# HV.net
KiCad netlist of a schematic drawn in Altium Designer
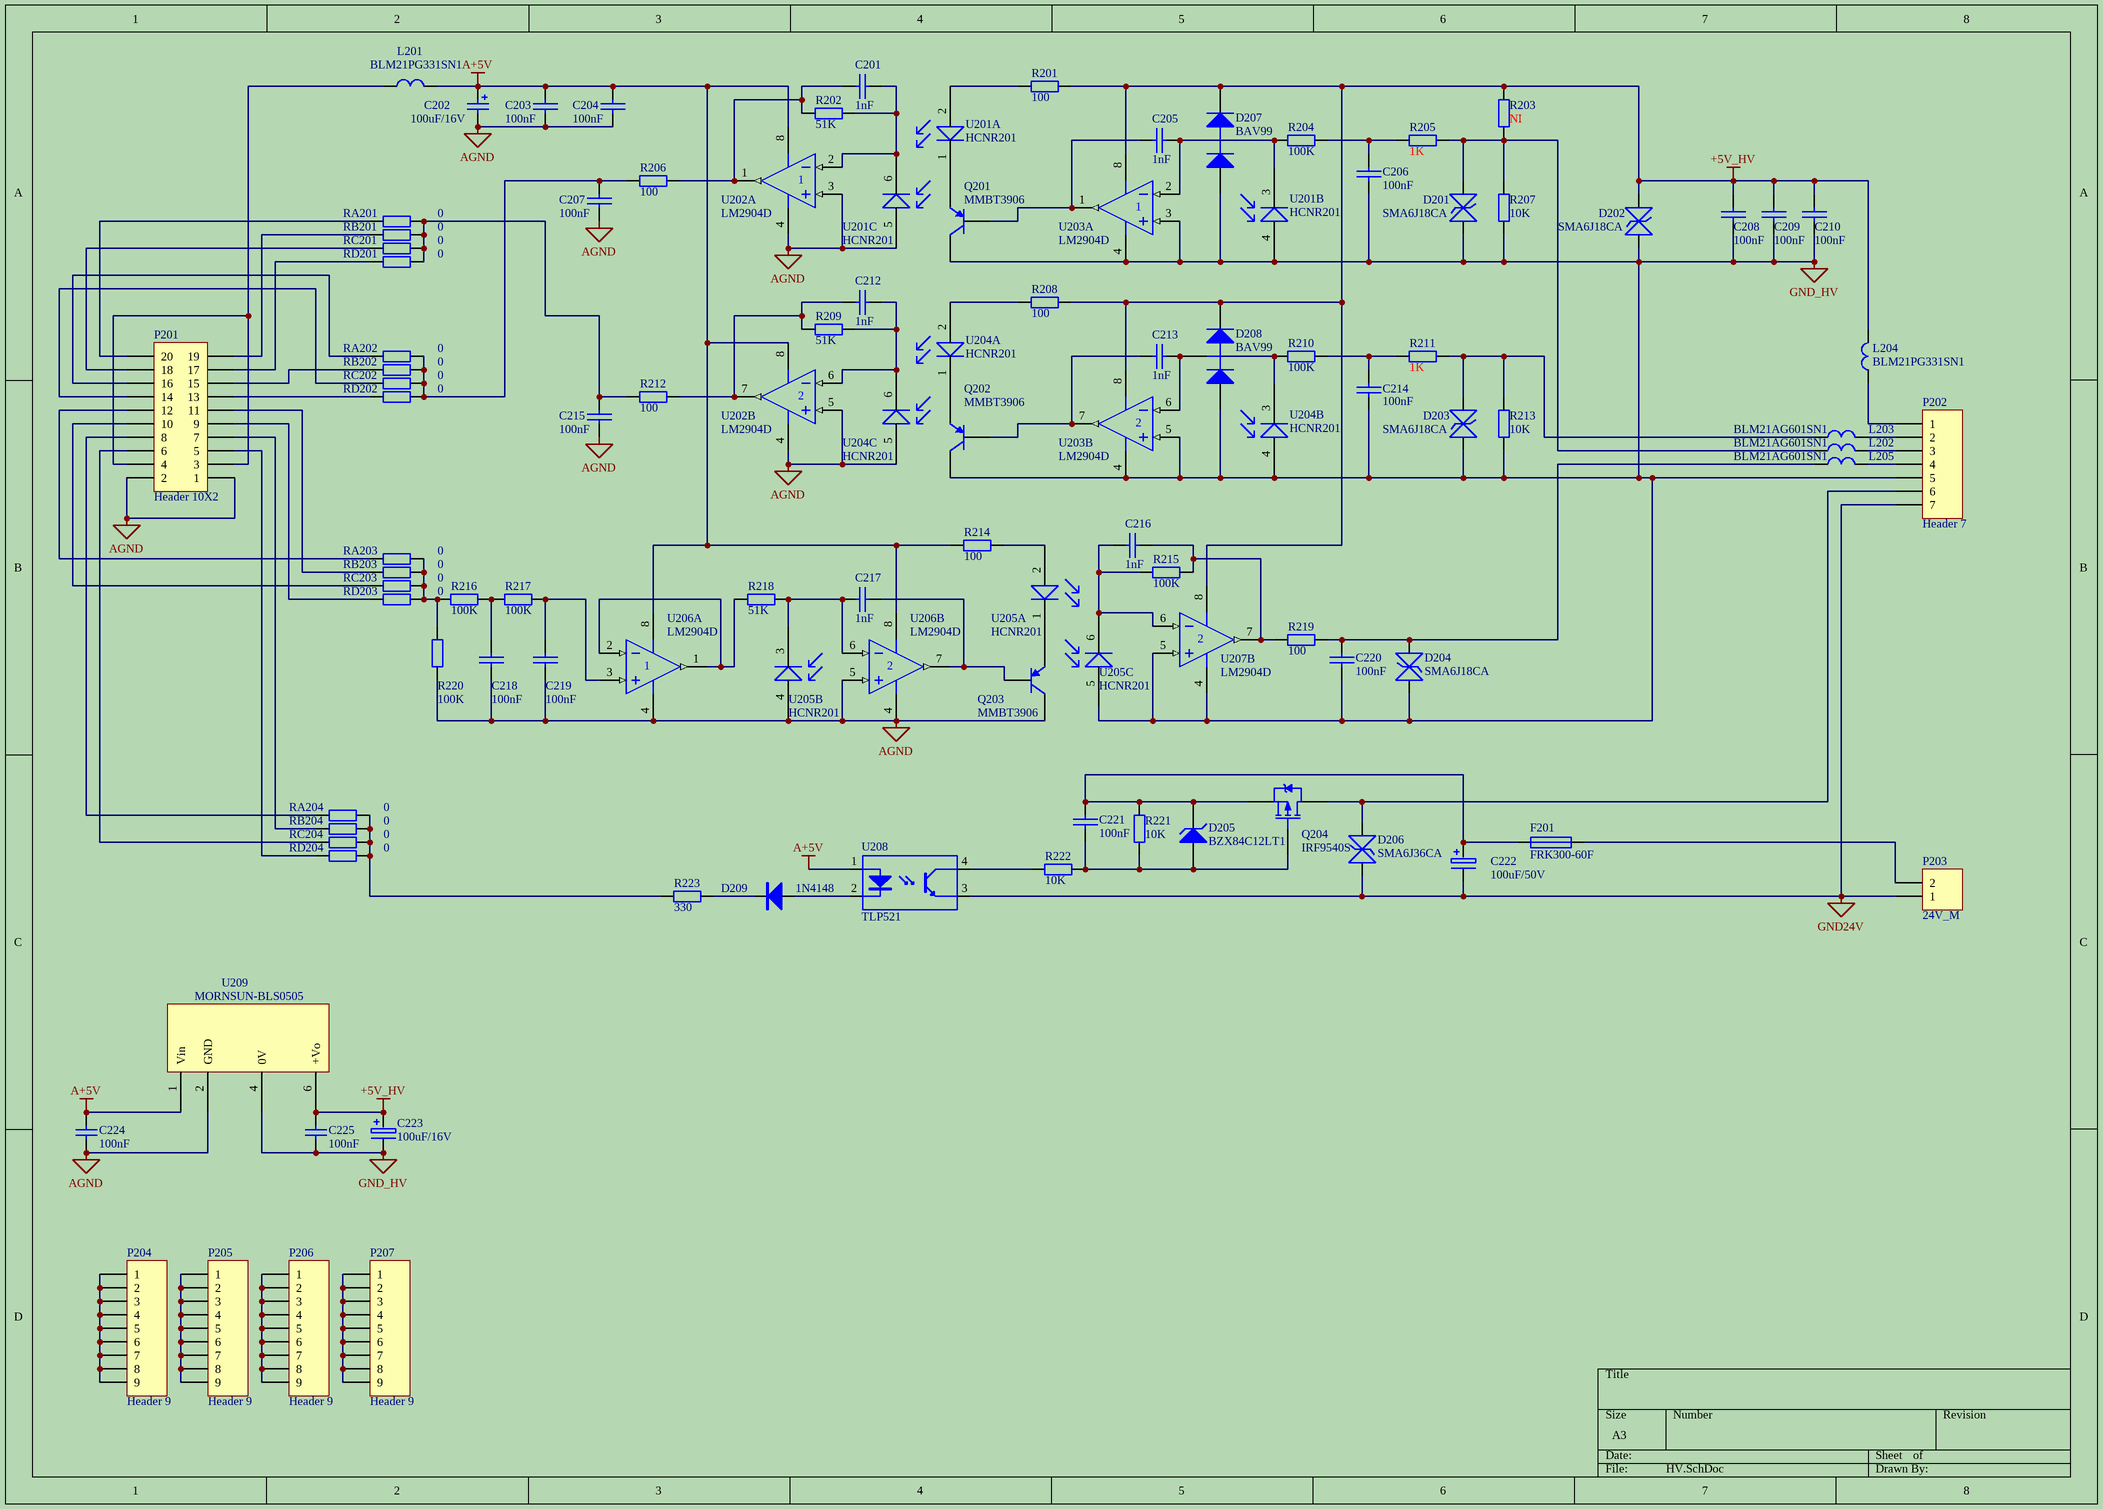
[diagram p0: HV.SchDoc]

(export (version "E")
  (design (tool "Eeschema 10.0.6"))
  (components
    (comp (ref "C201")
      (value "1nF")
      (footprint "贴片元器件:C0805")
      (description "Capacitor")
      (libsource (lib "*") (part "CAP"))
    )
    (comp (ref "C202")
      (value "100uF/16V")
      (footprint "CD1/2")
      (description "Polarized Capacitor (Axial)")
      (fields (field (name "PUBLISHER") "Altium Limited"))
      (libsource (lib "Miscellaneous Devices") (part "Cap Pol2"))
    )
    (comp (ref "C203")
      (value "100nF")
      (footprint "贴片元器件:C0805")
      (description "Capacitor")
      (libsource (lib "*") (part "CC"))
    )
    (comp (ref "C204")
      (value "100nF")
      (footprint "贴片元器件:C0805")
      (description "Capacitor")
      (libsource (lib "*") (part "CC"))
    )
    (comp (ref "C205")
      (value "1nF")
      (footprint "C0805")
      (description "Capacitor")
      (libsource (lib "*") (part "CAP"))
    )
    (comp (ref "C206")
      (value "100nF")
      (footprint "贴片元器件:C0805")
      (description "Capacitor")
      (libsource (lib "*") (part "CC"))
    )
    (comp (ref "C207")
      (value "100nF")
      (footprint "贴片元器件:C0805")
      (description "Capacitor")
      (libsource (lib "*") (part "CC"))
    )
    (comp (ref "C208")
      (value "100nF")
      (footprint "贴片元器件:C0805")
      (description "Capacitor")
      (libsource (lib "*") (part "CC"))
    )
    (comp (ref "C209")
      (value "100nF")
      (footprint "贴片元器件:C0805")
      (description "Capacitor")
      (libsource (lib "*") (part "CC"))
    )
    (comp (ref "C210")
      (value "100nF")
      (footprint "贴片元器件:C0805")
      (description "Capacitor")
      (libsource (lib "*") (part "CC"))
    )
    (comp (ref "C212")
      (value "1nF")
      (footprint "贴片元器件:C0805")
      (description "Capacitor")
      (libsource (lib "*") (part "CAP"))
    )
    (comp (ref "C213")
      (value "1nF")
      (footprint "C0805")
      (description "Capacitor")
      (libsource (lib "*") (part "CAP"))
    )
    (comp (ref "C214")
      (value "100nF")
      (footprint "贴片元器件:C0805")
      (description "Capacitor")
      (libsource (lib "*") (part "CC"))
    )
    (comp (ref "C215")
      (value "100nF")
      (footprint "贴片元器件:C0805")
      (description "Capacitor")
      (libsource (lib "*") (part "CC"))
    )
    (comp (ref "C216")
      (value "1nF")
      (footprint "贴片元器件:C0805")
      (description "Capacitor")
      (libsource (lib "*") (part "CAP"))
    )
    (comp (ref "C217")
      (value "1nF")
      (footprint "C0805")
      (description "Capacitor")
      (libsource (lib "*") (part "CAP"))
    )
    (comp (ref "C218")
      (value "100nF")
      (footprint "贴片元器件:C0805")
      (description "Capacitor")
      (libsource (lib "*") (part "CC"))
    )
    (comp (ref "C219")
      (value "100nF")
      (footprint "贴片元器件:C0805")
      (description "Capacitor")
      (libsource (lib "*") (part "CC"))
    )
    (comp (ref "C220")
      (value "100nF")
      (footprint "贴片元器件:C0805")
      (description "Capacitor")
      (libsource (lib "*") (part "CC"))
    )
    (comp (ref "C221")
      (value "100nF")
      (footprint "贴片元器件:C0805")
      (description "Capacitor")
      (libsource (lib "*") (part "CC"))
    )
    (comp (ref "C222")
      (value "100uF/50V")
      (footprint "CD2/4")
      (description "Electrolytic Capacitor")
      (libsource (lib "Devices") (part "CD1"))
    )
    (comp (ref "C223")
      (value "100uF/16V")
      (footprint "CD1/2")
      (description "Electrolytic Capacitor")
      (libsource (lib "Devices") (part "CD1"))
    )
    (comp (ref "C224")
      (value "100nF")
      (footprint "贴片元器件:C0805")
      (description "Capacitor")
      (fields (field (name "PUBLISHER") "Altium Limited"))
      (libsource (lib "Miscellaneous Devices") (part "Cap"))
    )
    (comp (ref "C225")
      (value "100nF")
      (footprint "贴片元器件:C0805")
      (description "Capacitor")
      (fields (field (name "PUBLISHER") "Altium Limited"))
      (libsource (lib "Miscellaneous Devices") (part "Cap"))
    )
    (comp (ref "D201") (value "SMA6J18CA") (footprint "SMA") (libsource (lib "IC") (part "TVS")))
    (comp (ref "D202") (value "SMA6J18CA") (footprint "SMA") (libsource (lib "IC") (part "TVS")))
    (comp (ref "D203") (value "SMA6J18CA") (footprint "SMA") (libsource (lib "IC") (part "TVS")))
    (comp (ref "D204") (value "SMA6J18CA") (footprint "SMA") (libsource (lib "IC") (part "TVS")))
    (comp (ref "D205")
      (value "BZX84C12LT1")
      (footprint "318-07")
      (description "Zener Voltage Regulator Diode")
      (fields (field (name "PUBLISHER") "Altium Limited"))
      (libsource (lib "Motorola Discrete Diode") (part "BZX84C12LT1"))
    )
    (comp (ref "D206") (value "SMA6J36CA") (footprint "SMA") (libsource (lib "IC") (part "TVS")))
    (comp (ref "D207")
      (value "BAV99")
      (footprint "SOT-23")
      (description "Silicon Switching Diode Array for High-Speed Switching")
      (fields (field (name "PUBLISHER") "Altium Limited"))
      (libsource (lib "Infineon Discrete Diode") (part "BAV99"))
    )
    (comp (ref "D208")
      (value "BAV99")
      (footprint "SOT-23")
      (description "Silicon Switching Diode Array for High-Speed Switching")
      (fields (field (name "PUBLISHER") "Altium Limited"))
      (libsource (lib "Infineon Discrete Diode") (part "BAV99"))
    )
    (comp (ref "D209") (value "1N4148") (footprint "D1206") (libsource (lib "Devices") (part "2JG")))
    (comp (ref "F201")
      (value "FRK300-60F")
      (footprint "RAD-0.2")
      (description "Fuse")
      (libsource (lib "Devices") (part "FUSE1"))
    )
    (comp (ref "L201") (value "BLM21PG331SN1") (footprint "L0805") (libsource (lib "Devices") (part "L1")))
    (comp (ref "L202") (value "BLM21AG601SN1") (footprint "L0805") (libsource (lib "Devices") (part "L1")))
    (comp (ref "L203") (value "BLM21AG601SN1") (footprint "L0805") (libsource (lib "Devices") (part "L1")))
    (comp (ref "L204") (value "BLM21PG331SN1") (footprint "L0805") (libsource (lib "Devices") (part "L1")))
    (comp (ref "L205") (value "BLM21AG601SN1") (footprint "L0805") (libsource (lib "") (part "L1_1")))
    (comp (ref "P201")
      (value "Header 10X2")
      (footprint "IDC20-EJ")
      (description "Header, 10-Pin, Dual row")
      (fields (field (name "PUBLISHER") "Altium Limited"))
      (libsource (lib "Miscellaneous Connectors") (part "Header 10X2"))
    )
    (comp (ref "P202")
      (value "Header 7")
      (footprint "3.96-7")
      (description "Header, 7-Pin")
      (fields (field (name "PUBLISHER") "Altium Limited"))
      (libsource (lib "Miscellaneous Connectors") (part "Header 7"))
    )
    (comp (ref "P203")
      (value "24V_M")
      (footprint "3.96-2")
      (description "Header, 2-Pin")
      (fields (field (name "PUBLISHER") "Altium Limited"))
      (libsource (lib "Miscellaneous Connectors") (part "Header 2"))
    )
    (comp (ref "P204")
      (value "Header 9")
      (footprint "LK")
      (description "Header, 9-Pin")
      (fields (field (name "PUBLISHER") "Altium Limited"))
      (libsource (lib "Miscellaneous Connectors") (part "Header 9"))
    )
    (comp (ref "P205")
      (value "Header 9")
      (footprint "LK")
      (description "Header, 9-Pin")
      (fields (field (name "PUBLISHER") "Altium Limited"))
      (libsource (lib "Miscellaneous Connectors") (part "Header 9"))
    )
    (comp (ref "P206")
      (value "Header 9")
      (footprint "LK")
      (description "Header, 9-Pin")
      (fields (field (name "PUBLISHER") "Altium Limited"))
      (libsource (lib "Miscellaneous Connectors") (part "Header 9"))
    )
    (comp (ref "P207")
      (value "Header 9")
      (footprint "LK")
      (description "Header, 9-Pin")
      (fields (field (name "PUBLISHER") "Altium Limited"))
      (libsource (lib "Miscellaneous Connectors") (part "Header 9"))
    )
    (comp (ref "Q201")
      (value "MMBT3906")
      (footprint "SOT23_N")
      (description "PNP Switching Transistor")
      (fields (field (name "PUBLISHER") "Altium Limited"))
      (libsource (lib "Philips Discrete BJT - Low Power") (part "MMBT3906"))
    )
    (comp (ref "Q202")
      (value "MMBT3906")
      (footprint "SOT23_N")
      (description "PNP Switching Transistor")
      (fields (field (name "PUBLISHER") "Altium Limited"))
      (libsource (lib "Philips Discrete BJT - Low Power") (part "MMBT3906"))
    )
    (comp (ref "Q203")
      (value "MMBT3906")
      (footprint "SOT23_N")
      (description "PNP Switching Transistor")
      (fields (field (name "PUBLISHER") "Altium Limited"))
      (libsource (lib "Philips Discrete BJT - Low Power") (part "MMBT3906"))
    )
    (comp (ref "Q204")
      (value "IRF9540S")
      (footprint "D2PAK_N")
      (description "HEXFET P-Channel Power MOSFET")
      (fields (field (name "PUBLISHER") "Altium Limited"))
      (libsource (lib "IR Discrete MOSFET - Power") (part "IRF9540S"))
    )
    (comp (ref "R201")
      (value "100")
      (footprint "R0805")
      (description "Resistor")
      (fields (field (name "PUBLISHER") "Altium Limited"))
      (libsource (lib "") (part "Res2_1"))
    )
    (comp (ref "R202")
      (value "51K")
      (footprint "R0805")
      (description "Resistor")
      (fields (field (name "PUBLISHER") "Altium Limited"))
      (libsource (lib "") (part "Res2_2"))
    )
    (comp (ref "R203")
      (value "NI")
      (footprint "R0805")
      (description "Resistor")
      (fields (field (name "PUBLISHER") "Altium Limited"))
      (libsource (lib "") (part "Res2_3"))
    )
    (comp (ref "R204")
      (value "100K")
      (footprint "R0805")
      (description "Resistor")
      (fields (field (name "PUBLISHER") "Altium Limited"))
      (libsource (lib "") (part "Res2_2"))
    )
    (comp (ref "R205")
      (value "1K")
      (footprint "R0805")
      (description "Resistor")
      (fields (field (name "PUBLISHER") "Altium Limited"))
      (libsource (lib "") (part "Res2_2"))
    )
    (comp (ref "R206")
      (value "100")
      (footprint "R0805")
      (description "Resistor")
      (fields (field (name "PUBLISHER") "Altium Limited"))
      (libsource (lib "") (part "Res2_1"))
    )
    (comp (ref "R207")
      (value "10K")
      (footprint "R0805")
      (description "Resistor")
      (fields (field (name "PUBLISHER") "Altium Limited"))
      (libsource (lib "") (part "Res2_4"))
    )
    (comp (ref "R208")
      (value "100")
      (footprint "R0805")
      (description "Resistor")
      (fields (field (name "PUBLISHER") "Altium Limited"))
      (libsource (lib "") (part "Res2_1"))
    )
    (comp (ref "R209")
      (value "51K")
      (footprint "R0805")
      (description "Resistor")
      (fields (field (name "PUBLISHER") "Altium Limited"))
      (libsource (lib "") (part "Res2_2"))
    )
    (comp (ref "R210")
      (value "100K")
      (footprint "R0805")
      (description "Resistor")
      (fields (field (name "PUBLISHER") "Altium Limited"))
      (libsource (lib "") (part "Res2_2"))
    )
    (comp (ref "R211")
      (value "1K")
      (footprint "R0805")
      (description "Resistor")
      (fields (field (name "PUBLISHER") "Altium Limited"))
      (libsource (lib "") (part "Res2_2"))
    )
    (comp (ref "R212")
      (value "100")
      (footprint "R0805")
      (description "Resistor")
      (fields (field (name "PUBLISHER") "Altium Limited"))
      (libsource (lib "") (part "Res2_1"))
    )
    (comp (ref "R213")
      (value "10K")
      (footprint "R0805")
      (description "Resistor")
      (fields (field (name "PUBLISHER") "Altium Limited"))
      (libsource (lib "") (part "Res2_4"))
    )
    (comp (ref "R214")
      (value "100")
      (footprint "R0805")
      (description "Resistor")
      (fields (field (name "PUBLISHER") "Altium Limited"))
      (libsource (lib "") (part "Res2_5"))
    )
    (comp (ref "R215")
      (value "100K")
      (footprint "R0805")
      (description "Resistor")
      (fields (field (name "PUBLISHER") "Altium Limited"))
      (libsource (lib "") (part "Res2_3"))
    )
    (comp (ref "R216")
      (value "100K")
      (footprint "R0805")
      (description "Resistor")
      (fields (field (name "PUBLISHER") "Altium Limited"))
      (libsource (lib "") (part "Res2_3"))
    )
    (comp (ref "R217")
      (value "100K")
      (footprint "R0805")
      (description "Resistor")
      (fields (field (name "PUBLISHER") "Altium Limited"))
      (libsource (lib "") (part "Res2_3"))
    )
    (comp (ref "R218")
      (value "51K")
      (footprint "R0805")
      (description "Resistor")
      (fields (field (name "PUBLISHER") "Altium Limited"))
      (libsource (lib "") (part "Res2_3"))
    )
    (comp (ref "R219")
      (value "100")
      (footprint "R0805")
      (description "Resistor")
      (fields (field (name "PUBLISHER") "Altium Limited"))
      (libsource (lib "") (part "Res2_5"))
    )
    (comp (ref "R220")
      (value "100K")
      (footprint "R0805")
      (description "Resistor")
      (fields (field (name "PUBLISHER") "Altium Limited"))
      (libsource (lib "") (part "Res2_4"))
    )
    (comp (ref "R221")
      (value "10K")
      (footprint "R0805")
      (description "Resistor")
      (fields (field (name "PUBLISHER") "Altium Limited"))
      (libsource (lib "Miscellaneous Devices") (part "Res2"))
    )
    (comp (ref "R222")
      (value "10K")
      (footprint "R0805")
      (description "Resistor")
      (fields (field (name "PUBLISHER") "Altium Limited"))
      (libsource (lib "") (part "Res2_6"))
    )
    (comp (ref "R223")
      (value "330")
      (footprint "R0805")
      (description "Resistor")
      (fields (field (name "PUBLISHER") "Altium Limited"))
      (libsource (lib "") (part "Res2_5"))
    )
    (comp (ref "RA201")
      (value "0")
      (footprint "R0805")
      (description "Resistor")
      (fields (field (name "PUBLISHER") "Altium Limited"))
      (libsource (lib "") (part "Res2_1"))
    )
    (comp (ref "RA202")
      (value "0")
      (footprint "R0805")
      (description "Resistor")
      (fields (field (name "PUBLISHER") "Altium Limited"))
      (libsource (lib "") (part "Res2_1"))
    )
    (comp (ref "RA203")
      (value "0")
      (footprint "R0805")
      (description "Resistor")
      (fields (field (name "PUBLISHER") "Altium Limited"))
      (libsource (lib "") (part "Res2_1"))
    )
    (comp (ref "RA204")
      (value "0")
      (footprint "R0805")
      (description "Resistor")
      (fields (field (name "PUBLISHER") "Altium Limited"))
      (libsource (lib "") (part "Res2_1"))
    )
    (comp (ref "RB201")
      (value "0")
      (footprint "R0805")
      (description "Resistor")
      (fields (field (name "PUBLISHER") "Altium Limited"))
      (libsource (lib "") (part "Res2_1"))
    )
    (comp (ref "RB202")
      (value "0")
      (footprint "R0805")
      (description "Resistor")
      (fields (field (name "PUBLISHER") "Altium Limited"))
      (libsource (lib "") (part "Res2_1"))
    )
    (comp (ref "RB203")
      (value "0")
      (footprint "R0805")
      (description "Resistor")
      (fields (field (name "PUBLISHER") "Altium Limited"))
      (libsource (lib "") (part "Res2_1"))
    )
    (comp (ref "RB204")
      (value "0")
      (footprint "R0805")
      (description "Resistor")
      (fields (field (name "PUBLISHER") "Altium Limited"))
      (libsource (lib "") (part "Res2_1"))
    )
    (comp (ref "RC201")
      (value "0")
      (footprint "R0805")
      (description "Resistor")
      (fields (field (name "PUBLISHER") "Altium Limited"))
      (libsource (lib "") (part "Res2_1"))
    )
    (comp (ref "RC202")
      (value "0")
      (footprint "R0805")
      (description "Resistor")
      (fields (field (name "PUBLISHER") "Altium Limited"))
      (libsource (lib "") (part "Res2_1"))
    )
    (comp (ref "RC203")
      (value "0")
      (footprint "R0805")
      (description "Resistor")
      (fields (field (name "PUBLISHER") "Altium Limited"))
      (libsource (lib "") (part "Res2_1"))
    )
    (comp (ref "RC204")
      (value "0")
      (footprint "R0805")
      (description "Resistor")
      (fields (field (name "PUBLISHER") "Altium Limited"))
      (libsource (lib "") (part "Res2_1"))
    )
    (comp (ref "RD201")
      (value "0")
      (footprint "R0805")
      (description "Resistor")
      (fields (field (name "PUBLISHER") "Altium Limited"))
      (libsource (lib "") (part "Res2_1"))
    )
    (comp (ref "RD202")
      (value "0")
      (footprint "R0805")
      (description "Resistor")
      (fields (field (name "PUBLISHER") "Altium Limited"))
      (libsource (lib "") (part "Res2_1"))
    )
    (comp (ref "RD203")
      (value "0")
      (footprint "R0805")
      (description "Resistor")
      (fields (field (name "PUBLISHER") "Altium Limited"))
      (libsource (lib "") (part "Res2_1"))
    )
    (comp (ref "RD204")
      (value "0")
      (footprint "R0805")
      (description "Resistor")
      (fields (field (name "PUBLISHER") "Altium Limited"))
      (libsource (lib "") (part "Res2_1"))
    )
    (comp (ref "U201") (value "HCNR201") (footprint "DIP-8-1") (libsource (lib "*") (part "HCNR201")))
    (comp (ref "U202")
      (value "LM2904D")
      (footprint "751-02_N")
      (description "Dual Low-Power Operational Amplifier")
      (fields (field (name "PUBLISHER") "Altium Limited"))
      (libsource (lib "Motorola Amplifier Operational Amplifier") (part "LM2904D"))
    )
    (comp (ref "U203")
      (value "LM2904D")
      (footprint "751-02_N")
      (description "Dual Low-Power Operational Amplifier")
      (fields (field (name "PUBLISHER") "Altium Limited"))
      (libsource (lib "Motorola Amplifier Operational Amplifier") (part "LM2904D"))
    )
    (comp (ref "U204") (value "HCNR201") (footprint "DIP-8-1") (libsource (lib "*") (part "HCNR201")))
    (comp (ref "U205") (value "HCNR201") (footprint "DIP-8-1") (libsource (lib "*") (part "HCNR201")))
    (comp (ref "U206")
      (value "LM2904D")
      (footprint "751-02_N")
      (description "Dual Low-Power Operational Amplifier")
      (fields (field (name "PUBLISHER") "Altium Limited"))
      (libsource (lib "Motorola Amplifier Operational Amplifier") (part "LM2904D"))
    )
    (comp (ref "U207")
      (value "LM2904D")
      (footprint "751-02_N")
      (description "Dual Low-Power Operational Amplifier")
      (fields (field (name "PUBLISHER") "Altium Limited"))
      (libsource (lib "Motorola Amplifier Operational Amplifier") (part "LM2904D"))
    )
    (comp (ref "U208") (value "TLP521") (footprint "DIP4") (libsource (lib "IC") (part "TLP521")))
    (comp (ref "U209")
      (value "MORNSUN-BLS0505")
      (footprint "MORNSUN-BLS")
      (description "MORNSUN Fixed input,Isolated,Unregulated Series DC/DC")
      (libsource (lib "稳压器件") (part "MORNSUN-BLS"))
    )
  )
  (nets
    (net (code "1") (name "+5V_HV") (class "Default")
      (node (ref "C208") (pin "2") (pinfunction "2_2") (pintype "passive"))
      (node (ref "C209") (pin "2") (pinfunction "2_2") (pintype "passive"))
      (node (ref "C210") (pin "2") (pinfunction "2_2") (pintype "passive"))
      (node (ref "C223") (pin "1") (pinfunction "1_1") (pintype "passive"))
      (node (ref "C225") (pin "1") (pinfunction "1_1") (pintype "passive"))
      (node (ref "D202") (pin "1") (pinfunction "1_1") (pintype "passive"))
      (node (ref "D207") (pin "2") (pinfunction "K_2") (pintype "passive"))
      (node (ref "D208") (pin "2") (pinfunction "K_2") (pintype "passive"))
      (node (ref "L204") (pin "2") (pinfunction "2_2") (pintype "passive"))
      (node (ref "R201") (pin "1") (pinfunction "1_1") (pintype "passive"))
      (node (ref "R203") (pin "1") (pinfunction "1_1") (pintype "passive"))
      (node (ref "R208") (pin "1") (pinfunction "1_1") (pintype "passive"))
      (node (ref "U203") (pin "8") (pinfunction "V+_8") (pintype "power_in"))
      (node (ref "U207") (pin "8") (pinfunction "V+_8") (pintype "power_in"))
      (node (ref "U209") (pin "6") (pinfunction "+Vo_6") (pintype "passive"))
    )
    (net (code "2") (name "A+5V") (class "Default")
      (node (ref "C202") (pin "1") (pinfunction "1_1") (pintype "passive"))
      (node (ref "C203") (pin "2") (pinfunction "2_2") (pintype "passive"))
      (node (ref "C204") (pin "2") (pinfunction "2_2") (pintype "passive"))
      (node (ref "C224") (pin "1") (pinfunction "1_1") (pintype "passive"))
      (node (ref "L201") (pin "2") (pinfunction "2_2") (pintype "passive"))
      (node (ref "R214") (pin "1") (pinfunction "1_1") (pintype "passive"))
      (node (ref "U202") (pin "8") (pinfunction "V+_8") (pintype "power_in"))
      (node (ref "U206") (pin "8") (pinfunction "V+_8") (pintype "power_in"))
      (node (ref "U208") (pin "1") (pinfunction "A_1") (pintype "passive"))
      (node (ref "U209") (pin "1") (pinfunction "Vin_1") (pintype "passive"))
    )
    (net (code "3") (name "AGND") (class "Default")
      (node (ref "C202") (pin "2") (pinfunction "2_2") (pintype "passive"))
      (node (ref "C203") (pin "1") (pinfunction "1_1") (pintype "passive"))
      (node (ref "C204") (pin "1") (pinfunction "1_1") (pintype "passive"))
      (node (ref "C207") (pin "1") (pinfunction "1_1") (pintype "passive"))
      (node (ref "C215") (pin "1") (pinfunction "1_1") (pintype "passive"))
      (node (ref "C218") (pin "1") (pinfunction "1_1") (pintype "passive"))
      (node (ref "C219") (pin "1") (pinfunction "1_1") (pintype "passive"))
      (node (ref "C224") (pin "2") (pinfunction "2_2") (pintype "passive"))
      (node (ref "P201") (pin "1") (pinfunction "1_1") (pintype "passive"))
      (node (ref "P201") (pin "2") (pinfunction "2_2") (pintype "passive"))
      (node (ref "Q203") (pin "3") (pinfunction "C_3") (pintype "passive"))
      (node (ref "R220") (pin "1") (pinfunction "1_1") (pintype "passive"))
      (node (ref "U201") (pin "5") (pinfunction "+_5") (pintype "passive"))
      (node (ref "U202") (pin "3") (pinfunction "IN+_3") (pintype "input"))
      (node (ref "U202") (pin "4") (pinfunction "V-_4") (pintype "power_in"))
      (node (ref "U202") (pin "5") (pinfunction "IN+_5") (pintype "input"))
      (node (ref "U204") (pin "5") (pinfunction "+_5") (pintype "passive"))
      (node (ref "U205") (pin "4") (pinfunction "+_4") (pintype "passive"))
      (node (ref "U206") (pin "4") (pinfunction "V-_4") (pintype "power_in"))
      (node (ref "U206") (pin "5") (pinfunction "IN+_5") (pintype "input"))
      (node (ref "U209") (pin "2") (pinfunction "GND_2") (pintype "passive"))
    )
    (net (code "4") (name "GND24V") (class "Default")
      (node (ref "C222") (pin "2") (pinfunction "2_2") (pintype "passive"))
      (node (ref "D206") (pin "2") (pinfunction "2_2") (pintype "passive"))
      (node (ref "P202") (pin "7") (pinfunction "7_7") (pintype "passive"))
      (node (ref "P203") (pin "1") (pinfunction "1_1") (pintype "passive"))
      (node (ref "U208") (pin "3") (pinfunction "E_3") (pintype "passive"))
    )
    (net (code "5") (name "GND_HV") (class "Default")
      (node (ref "C206") (pin "1") (pinfunction "1_1") (pintype "passive"))
      (node (ref "C208") (pin "1") (pinfunction "1_1") (pintype "passive"))
      (node (ref "C209") (pin "1") (pinfunction "1_1") (pintype "passive"))
      (node (ref "C210") (pin "1") (pinfunction "1_1") (pintype "passive"))
      (node (ref "C214") (pin "1") (pinfunction "1_1") (pintype "passive"))
      (node (ref "C220") (pin "1") (pinfunction "1_1") (pintype "passive"))
      (node (ref "C223") (pin "2") (pinfunction "2_2") (pintype "passive"))
      (node (ref "C225") (pin "2") (pinfunction "2_2") (pintype "passive"))
      (node (ref "D201") (pin "2") (pinfunction "2_2") (pintype "passive"))
      (node (ref "D202") (pin "2") (pinfunction "2_2") (pintype "passive"))
      (node (ref "D203") (pin "2") (pinfunction "2_2") (pintype "passive"))
      (node (ref "D204") (pin "2") (pinfunction "2_2") (pintype "passive"))
      (node (ref "D207") (pin "1") (pinfunction "A_1") (pintype "passive"))
      (node (ref "D208") (pin "1") (pinfunction "A_1") (pintype "passive"))
      (node (ref "P202") (pin "5") (pinfunction "5_5") (pintype "passive"))
      (node (ref "Q201") (pin "3") (pinfunction "C_3") (pintype "passive"))
      (node (ref "Q202") (pin "3") (pinfunction "C_3") (pintype "passive"))
      (node (ref "R207") (pin "1") (pinfunction "1_1") (pintype "passive"))
      (node (ref "R213") (pin "1") (pinfunction "1_1") (pintype "passive"))
      (node (ref "U201") (pin "4") (pinfunction "+_4") (pintype "passive"))
      (node (ref "U203") (pin "3") (pinfunction "IN+_3") (pintype "input"))
      (node (ref "U203") (pin "4") (pinfunction "V-_4") (pintype "power_in"))
      (node (ref "U203") (pin "5") (pinfunction "IN+_5") (pintype "input"))
      (node (ref "U204") (pin "4") (pinfunction "+_4") (pintype "passive"))
      (node (ref "U205") (pin "5") (pinfunction "+_5") (pintype "passive"))
      (node (ref "U207") (pin "4") (pinfunction "V-_4") (pintype "power_in"))
      (node (ref "U207") (pin "5") (pinfunction "IN+_5") (pintype "input"))
      (node (ref "U209") (pin "4") (pinfunction "0V_4") (pintype "passive"))
    )
    (net (code "6") (name "Net-(C206-Pad2)") (class "Default")
      (node (ref "C206") (pin "2") (pinfunction "2_2") (pintype "passive"))
      (node (ref "R204") (pin "2") (pinfunction "2_2") (pintype "passive"))
      (node (ref "R205") (pin "1") (pinfunction "1_1") (pintype "passive"))
    )
    (net (code "7") (name "Net-(C207-Pad2)") (class "Default")
      (node (ref "C207") (pin "2") (pinfunction "2_2") (pintype "passive"))
      (node (ref "R206") (pin "2") (pinfunction "2_2") (pintype "passive"))
      (node (ref "RA202") (pin "1") (pinfunction "1_1") (pintype "passive"))
      (node (ref "RB202") (pin "1") (pinfunction "1_1") (pintype "passive"))
      (node (ref "RC202") (pin "1") (pinfunction "1_1") (pintype "passive"))
      (node (ref "RD202") (pin "1") (pinfunction "1_1") (pintype "passive"))
    )
    (net (code "8") (name "Net-(C214-Pad2)") (class "Default")
      (node (ref "C214") (pin "2") (pinfunction "2_2") (pintype "passive"))
      (node (ref "R210") (pin "2") (pinfunction "2_2") (pintype "passive"))
      (node (ref "R211") (pin "1") (pinfunction "1_1") (pintype "passive"))
    )
    (net (code "9") (name "Net-(C215-Pad2)") (class "Default")
      (node (ref "C215") (pin "2") (pinfunction "2_2") (pintype "passive"))
      (node (ref "R212") (pin "2") (pinfunction "2_2") (pintype "passive"))
      (node (ref "RA201") (pin "1") (pinfunction "1_1") (pintype "passive"))
      (node (ref "RB201") (pin "1") (pinfunction "1_1") (pintype "passive"))
      (node (ref "RC201") (pin "1") (pinfunction "1_1") (pintype "passive"))
      (node (ref "RD201") (pin "1") (pinfunction "1_1") (pintype "passive"))
    )
    (net (code "10") (name "Net-(C218-Pad2)") (class "Default")
      (node (ref "C218") (pin "2") (pinfunction "2_2") (pintype "passive"))
      (node (ref "R216") (pin "1") (pinfunction "1_1") (pintype "passive"))
      (node (ref "R217") (pin "2") (pinfunction "2_2") (pintype "passive"))
    )
    (net (code "11") (name "Net-(C220-Pad2)") (class "Default")
      (node (ref "C220") (pin "2") (pinfunction "2_2") (pintype "passive"))
      (node (ref "D204") (pin "1") (pinfunction "1_1") (pintype "passive"))
      (node (ref "L205") (pin "2") (pinfunction "2_2") (pintype "passive"))
      (node (ref "R219") (pin "2") (pinfunction "2_2") (pintype "passive"))
    )
    (net (code "12") (name "Net-(D201-Pad1)") (class "Default")
      (node (ref "D201") (pin "1") (pinfunction "1_1") (pintype "passive"))
      (node (ref "L202") (pin "1") (pinfunction "1_1") (pintype "passive"))
      (node (ref "R203") (pin "2") (pinfunction "2_2") (pintype "passive"))
      (node (ref "R205") (pin "2") (pinfunction "2_2") (pintype "passive"))
      (node (ref "R207") (pin "2") (pinfunction "2_2") (pintype "passive"))
    )
    (net (code "13") (name "Net-(D203-Pad1)") (class "Default")
      (node (ref "D203") (pin "1") (pinfunction "1_1") (pintype "passive"))
      (node (ref "L203") (pin "1") (pinfunction "1_1") (pintype "passive"))
      (node (ref "R211") (pin "2") (pinfunction "2_2") (pintype "passive"))
      (node (ref "R213") (pin "2") (pinfunction "2_2") (pintype "passive"))
    )
    (net (code "14") (name "Net-(D205-A)") (class "Default")
      (node (ref "C221") (pin "1") (pinfunction "1_1") (pintype "passive"))
      (node (ref "D205") (pin "1") (pinfunction "A_1") (pintype "passive"))
      (node (ref "Q204") (pin "1") (pinfunction "G_1") (pintype "passive"))
      (node (ref "R221") (pin "1") (pinfunction "1_1") (pintype "passive"))
      (node (ref "R222") (pin "1") (pinfunction "1_1") (pintype "passive"))
    )
    (net (code "15") (name "Net-(D205-K)") (class "Default")
      (node (ref "C221") (pin "2") (pinfunction "2_2") (pintype "passive"))
      (node (ref "C222") (pin "1") (pinfunction "1_1") (pintype "passive"))
      (node (ref "D205") (pin "3") (pinfunction "K_3") (pintype "passive"))
      (node (ref "F201") (pin "2") (pinfunction "2_2") (pintype "passive"))
      (node (ref "Q204") (pin "3") (pinfunction "S_3") (pintype "passive"))
      (node (ref "R221") (pin "2") (pinfunction "2_2") (pintype "passive"))
    )
    (net (code "16") (name "Net-(D207-C)") (class "Default")
      (node (ref "C205") (pin "1") (pinfunction "1_1") (pintype "passive"))
      (node (ref "D207") (pin "3") (pinfunction "C_3") (pintype "passive"))
      (node (ref "R204") (pin "1") (pinfunction "1_1") (pintype "passive"))
      (node (ref "U201") (pin "3") (pinfunction "-_3") (pintype "passive"))
      (node (ref "U203") (pin "2") (pinfunction "IN-_2") (pintype "input"))
    )
    (net (code "17") (name "Net-(D208-C)") (class "Default")
      (node (ref "C213") (pin "1") (pinfunction "1_1") (pintype "passive"))
      (node (ref "D208") (pin "3") (pinfunction "C_3") (pintype "passive"))
      (node (ref "R210") (pin "1") (pinfunction "1_1") (pintype "passive"))
      (node (ref "U203") (pin "6") (pinfunction "IN-_6") (pintype "input"))
      (node (ref "U204") (pin "3") (pinfunction "-_3") (pintype "passive"))
    )
    (net (code "18") (name "Net-(D209-A)") (class "Default")
      (node (ref "D209") (pin "1") (pinfunction "A_1") (pintype "passive"))
      (node (ref "U208") (pin "2") (pinfunction "K_2") (pintype "passive"))
    )
    (net (code "19") (name "Net-(D209-K)") (class "Default")
      (node (ref "D209") (pin "2") (pinfunction "K_2") (pintype "passive"))
      (node (ref "R223") (pin "2") (pinfunction "2_2") (pintype "passive"))
    )
    (net (code "20") (name "Net-(F201-Pad1)") (class "Default")
      (node (ref "F201") (pin "1") (pinfunction "1_1") (pintype "passive"))
      (node (ref "P203") (pin "2") (pinfunction "2_2") (pintype "passive"))
    )
    (net (code "21") (name "Net-(L201-Pad1)") (class "Default")
      (node (ref "L201") (pin "1") (pinfunction "1_1") (pintype "passive"))
      (node (ref "P201") (pin "3") (pinfunction "3_3") (pintype "passive"))
      (node (ref "P201") (pin "4") (pinfunction "4_4") (pintype "passive"))
    )
    (net (code "22") (name "Net-(L202-Pad2)") (class "Default")
      (node (ref "L202") (pin "2") (pinfunction "2_2") (pintype "passive"))
      (node (ref "P202") (pin "3") (pinfunction "3_3") (pintype "passive"))
    )
    (net (code "23") (name "Net-(L203-Pad2)") (class "Default")
      (node (ref "L203") (pin "2") (pinfunction "2_2") (pintype "passive"))
      (node (ref "P202") (pin "2") (pinfunction "2_2") (pintype "passive"))
    )
    (net (code "24") (name "Net-(L204-Pad1)") (class "Default")
      (node (ref "L204") (pin "1") (pinfunction "1_1") (pintype "passive"))
      (node (ref "P202") (pin "1") (pinfunction "1_1") (pintype "passive"))
    )
    (net (code "25") (name "Net-(L205-Pad1)") (class "Default")
      (node (ref "L205") (pin "1") (pinfunction "1_1") (pintype "passive"))
      (node (ref "P202") (pin "4") (pinfunction "4_4") (pintype "passive"))
    )
    (net (code "26") (name "Net-(P201-Pad5)") (class "Default")
      (node (ref "P201") (pin "5") (pinfunction "5_5") (pintype "passive"))
      (node (ref "RD204") (pin "2") (pinfunction "2_2") (pintype "passive"))
    )
    (net (code "27") (name "Net-(P201-Pad6)") (class "Default")
      (node (ref "P201") (pin "6") (pinfunction "6_6") (pintype "passive"))
      (node (ref "RC204") (pin "2") (pinfunction "2_2") (pintype "passive"))
    )
    (net (code "28") (name "Net-(P201-Pad7)") (class "Default")
      (node (ref "P201") (pin "7") (pinfunction "7_7") (pintype "passive"))
      (node (ref "RB204") (pin "2") (pinfunction "2_2") (pintype "passive"))
    )
    (net (code "29") (name "Net-(P201-Pad8)") (class "Default")
      (node (ref "P201") (pin "8") (pinfunction "8_8") (pintype "passive"))
      (node (ref "RA204") (pin "2") (pinfunction "2_2") (pintype "passive"))
    )
    (net (code "30") (name "Net-(P201-Pad9)") (class "Default")
      (node (ref "P201") (pin "9") (pinfunction "9_9") (pintype "passive"))
      (node (ref "RD203") (pin "2") (pinfunction "2_2") (pintype "passive"))
    )
    (net (code "31") (name "Net-(P201-Pad10)") (class "Default")
      (node (ref "P201") (pin "10") (pinfunction "10_10") (pintype "passive"))
      (node (ref "RC203") (pin "2") (pinfunction "2_2") (pintype "passive"))
    )
    (net (code "32") (name "Net-(P201-Pad11)") (class "Default")
      (node (ref "P201") (pin "11") (pinfunction "11_11") (pintype "passive"))
      (node (ref "RB203") (pin "2") (pinfunction "2_2") (pintype "passive"))
    )
    (net (code "33") (name "Net-(P201-Pad12)") (class "Default")
      (node (ref "P201") (pin "12") (pinfunction "12_12") (pintype "passive"))
      (node (ref "RA203") (pin "2") (pinfunction "2_2") (pintype "passive"))
    )
    (net (code "34") (name "Net-(P201-Pad13)") (class "Default")
      (node (ref "P201") (pin "13") (pinfunction "13_13") (pintype "passive"))
      (node (ref "RD202") (pin "2") (pinfunction "2_2") (pintype "passive"))
    )
    (net (code "35") (name "Net-(P201-Pad14)") (class "Default")
      (node (ref "P201") (pin "14") (pinfunction "14_14") (pintype "passive"))
      (node (ref "RC202") (pin "2") (pinfunction "2_2") (pintype "passive"))
    )
    (net (code "36") (name "Net-(P201-Pad15)") (class "Default")
      (node (ref "P201") (pin "15") (pinfunction "15_15") (pintype "passive"))
      (node (ref "RB202") (pin "2") (pinfunction "2_2") (pintype "passive"))
    )
    (net (code "37") (name "Net-(P201-Pad16)") (class "Default")
      (node (ref "P201") (pin "16") (pinfunction "16_16") (pintype "passive"))
      (node (ref "RA202") (pin "2") (pinfunction "2_2") (pintype "passive"))
    )
    (net (code "38") (name "Net-(P201-Pad17)") (class "Default")
      (node (ref "P201") (pin "17") (pinfunction "17_17") (pintype "passive"))
      (node (ref "RD201") (pin "2") (pinfunction "2_2") (pintype "passive"))
    )
    (net (code "39") (name "Net-(P201-Pad18)") (class "Default")
      (node (ref "P201") (pin "18") (pinfunction "18_18") (pintype "passive"))
      (node (ref "RC201") (pin "2") (pinfunction "2_2") (pintype "passive"))
    )
    (net (code "40") (name "Net-(P201-Pad19)") (class "Default")
      (node (ref "P201") (pin "19") (pinfunction "19_19") (pintype "passive"))
      (node (ref "RB201") (pin "2") (pinfunction "2_2") (pintype "passive"))
    )
    (net (code "41") (name "Net-(P201-Pad20)") (class "Default")
      (node (ref "P201") (pin "20") (pinfunction "20_20") (pintype "passive"))
      (node (ref "RA201") (pin "2") (pinfunction "2_2") (pintype "passive"))
    )
    (net (code "42") (name "Net-(P204-Pad1)") (class "Default")
      (node (ref "P204") (pin "1") (pinfunction "1_1") (pintype "passive"))
      (node (ref "P204") (pin "2") (pinfunction "2_2") (pintype "passive"))
      (node (ref "P204") (pin "3") (pinfunction "3_3") (pintype "passive"))
      (node (ref "P204") (pin "4") (pinfunction "4_4") (pintype "passive"))
      (node (ref "P204") (pin "5") (pinfunction "5_5") (pintype "passive"))
      (node (ref "P204") (pin "6") (pinfunction "6_6") (pintype "passive"))
      (node (ref "P204") (pin "7") (pinfunction "7_7") (pintype "passive"))
      (node (ref "P204") (pin "8") (pinfunction "8_8") (pintype "passive"))
      (node (ref "P204") (pin "9") (pinfunction "9_9") (pintype "passive"))
    )
    (net (code "43") (name "Net-(P205-Pad1)") (class "Default")
      (node (ref "P205") (pin "1") (pinfunction "1_1") (pintype "passive"))
      (node (ref "P205") (pin "2") (pinfunction "2_2") (pintype "passive"))
      (node (ref "P205") (pin "3") (pinfunction "3_3") (pintype "passive"))
      (node (ref "P205") (pin "4") (pinfunction "4_4") (pintype "passive"))
      (node (ref "P205") (pin "5") (pinfunction "5_5") (pintype "passive"))
      (node (ref "P205") (pin "6") (pinfunction "6_6") (pintype "passive"))
      (node (ref "P205") (pin "7") (pinfunction "7_7") (pintype "passive"))
      (node (ref "P205") (pin "8") (pinfunction "8_8") (pintype "passive"))
      (node (ref "P205") (pin "9") (pinfunction "9_9") (pintype "passive"))
    )
    (net (code "44") (name "Net-(P206-Pad1)") (class "Default")
      (node (ref "P206") (pin "1") (pinfunction "1_1") (pintype "passive"))
      (node (ref "P206") (pin "2") (pinfunction "2_2") (pintype "passive"))
      (node (ref "P206") (pin "3") (pinfunction "3_3") (pintype "passive"))
      (node (ref "P206") (pin "4") (pinfunction "4_4") (pintype "passive"))
      (node (ref "P206") (pin "5") (pinfunction "5_5") (pintype "passive"))
      (node (ref "P206") (pin "6") (pinfunction "6_6") (pintype "passive"))
      (node (ref "P206") (pin "7") (pinfunction "7_7") (pintype "passive"))
      (node (ref "P206") (pin "8") (pinfunction "8_8") (pintype "passive"))
      (node (ref "P206") (pin "9") (pinfunction "9_9") (pintype "passive"))
    )
    (net (code "45") (name "Net-(P207-Pad1)") (class "Default")
      (node (ref "P207") (pin "1") (pinfunction "1_1") (pintype "passive"))
      (node (ref "P207") (pin "2") (pinfunction "2_2") (pintype "passive"))
      (node (ref "P207") (pin "3") (pinfunction "3_3") (pintype "passive"))
      (node (ref "P207") (pin "4") (pinfunction "4_4") (pintype "passive"))
      (node (ref "P207") (pin "5") (pinfunction "5_5") (pintype "passive"))
      (node (ref "P207") (pin "6") (pinfunction "6_6") (pintype "passive"))
      (node (ref "P207") (pin "7") (pinfunction "7_7") (pintype "passive"))
      (node (ref "P207") (pin "8") (pinfunction "8_8") (pintype "passive"))
      (node (ref "P207") (pin "9") (pinfunction "9_9") (pintype "passive"))
    )
    (net (code "46") (name "Net-(Q201-B)") (class "Default")
      (node (ref "C205") (pin "2") (pinfunction "2_2") (pintype "passive"))
      (node (ref "Q201") (pin "1") (pinfunction "B_1") (pintype "passive"))
      (node (ref "U203") (pin "1") (pinfunction "OUT_1") (pintype "output"))
    )
    (net (code "47") (name "Net-(Q201-E)") (class "Default")
      (node (ref "Q201") (pin "2") (pinfunction "E_2") (pintype "passive"))
      (node (ref "U201") (pin "1") (pinfunction "-_1") (pintype "passive"))
    )
    (net (code "48") (name "Net-(Q202-B)") (class "Default")
      (node (ref "C213") (pin "2") (pinfunction "2_2") (pintype "passive"))
      (node (ref "Q202") (pin "1") (pinfunction "B_1") (pintype "passive"))
      (node (ref "U203") (pin "7") (pinfunction "OUT_7") (pintype "output"))
    )
    (net (code "49") (name "Net-(Q202-E)") (class "Default")
      (node (ref "Q202") (pin "2") (pinfunction "E_2") (pintype "passive"))
      (node (ref "U204") (pin "1") (pinfunction "-_1") (pintype "passive"))
    )
    (net (code "50") (name "Net-(Q203-B)") (class "Default")
      (node (ref "C217") (pin "2") (pinfunction "2_2") (pintype "passive"))
      (node (ref "Q203") (pin "1") (pinfunction "B_1") (pintype "passive"))
      (node (ref "U206") (pin "7") (pinfunction "OUT_7") (pintype "output"))
    )
    (net (code "51") (name "Net-(Q203-E)") (class "Default")
      (node (ref "Q203") (pin "2") (pinfunction "E_2") (pintype "passive"))
      (node (ref "U205") (pin "1") (pinfunction "-_1") (pintype "passive"))
    )
    (net (code "52") (name "Net-(Q204-D)") (class "Default")
      (node (ref "D206") (pin "1") (pinfunction "1_1") (pintype "passive"))
      (node (ref "P202") (pin "6") (pinfunction "6_6") (pintype "passive"))
      (node (ref "Q204") (pin "2") (pinfunction "D_2") (pintype "passive"))
    )
    (net (code "53") (name "Net-(R216-Pad2)") (class "Default")
      (node (ref "R216") (pin "2") (pinfunction "2_2") (pintype "passive"))
      (node (ref "R220") (pin "2") (pinfunction "2_2") (pintype "passive"))
      (node (ref "RA203") (pin "1") (pinfunction "1_1") (pintype "passive"))
      (node (ref "RB203") (pin "1") (pinfunction "1_1") (pintype "passive"))
      (node (ref "RC203") (pin "1") (pinfunction "1_1") (pintype "passive"))
      (node (ref "RD203") (pin "1") (pinfunction "1_1") (pintype "passive"))
    )
    (net (code "54") (name "Net-(R223-Pad1)") (class "Default")
      (node (ref "R223") (pin "1") (pinfunction "1_1") (pintype "passive"))
      (node (ref "RA204") (pin "1") (pinfunction "1_1") (pintype "passive"))
      (node (ref "RB204") (pin "1") (pinfunction "1_1") (pintype "passive"))
      (node (ref "RC204") (pin "1") (pinfunction "1_1") (pintype "passive"))
      (node (ref "RD204") (pin "1") (pinfunction "1_1") (pintype "passive"))
    )
    (net (code "55") (name "Net-(U201A-+)") (class "Default")
      (node (ref "R201") (pin "2") (pinfunction "2_2") (pintype "passive"))
      (node (ref "U201") (pin "2") (pinfunction "+_2") (pintype "passive"))
    )
    (net (code "56") (name "Net-(U201C--)") (class "Default")
      (node (ref "C201") (pin "1") (pinfunction "1_1") (pintype "passive"))
      (node (ref "R202") (pin "2") (pinfunction "2_2") (pintype "passive"))
      (node (ref "U201") (pin "6") (pinfunction "-_6") (pintype "passive"))
      (node (ref "U202") (pin "2") (pinfunction "IN-_2") (pintype "input"))
    )
    (net (code "57") (name "Net-(U202A-OUT)") (class "Default")
      (node (ref "C201") (pin "2") (pinfunction "2_2") (pintype "passive"))
      (node (ref "R202") (pin "1") (pinfunction "1_1") (pintype "passive"))
      (node (ref "R206") (pin "1") (pinfunction "1_1") (pintype "passive"))
      (node (ref "U202") (pin "1") (pinfunction "OUT_1") (pintype "output"))
    )
    (net (code "58") (name "Net-(U202B-IN-)") (class "Default")
      (node (ref "C212") (pin "1") (pinfunction "1_1") (pintype "passive"))
      (node (ref "R209") (pin "2") (pinfunction "2_2") (pintype "passive"))
      (node (ref "U202") (pin "6") (pinfunction "IN-_6") (pintype "input"))
      (node (ref "U204") (pin "6") (pinfunction "-_6") (pintype "passive"))
    )
    (net (code "59") (name "Net-(U202B-OUT)") (class "Default")
      (node (ref "C212") (pin "2") (pinfunction "2_2") (pintype "passive"))
      (node (ref "R209") (pin "1") (pinfunction "1_1") (pintype "passive"))
      (node (ref "R212") (pin "1") (pinfunction "1_1") (pintype "passive"))
      (node (ref "U202") (pin "7") (pinfunction "OUT_7") (pintype "output"))
    )
    (net (code "60") (name "Net-(U204A-+)") (class "Default")
      (node (ref "R208") (pin "2") (pinfunction "2_2") (pintype "passive"))
      (node (ref "U204") (pin "2") (pinfunction "+_2") (pintype "passive"))
    )
    (net (code "61") (name "Net-(U205A-+)") (class "Default")
      (node (ref "R214") (pin "2") (pinfunction "2_2") (pintype "passive"))
      (node (ref "U205") (pin "2") (pinfunction "+_2") (pintype "passive"))
    )
    (net (code "62") (name "Net-(U205B--)") (class "Default")
      (node (ref "C217") (pin "1") (pinfunction "1_1") (pintype "passive"))
      (node (ref "R218") (pin "1") (pinfunction "1_1") (pintype "passive"))
      (node (ref "U205") (pin "3") (pinfunction "-_3") (pintype "passive"))
      (node (ref "U206") (pin "6") (pinfunction "IN-_6") (pintype "input"))
    )
    (net (code "63") (name "Net-(U205C--)") (class "Default")
      (node (ref "C216") (pin "1") (pinfunction "1_1") (pintype "passive"))
      (node (ref "R215") (pin "2") (pinfunction "2_2") (pintype "passive"))
      (node (ref "U205") (pin "6") (pinfunction "-_6") (pintype "passive"))
      (node (ref "U207") (pin "6") (pinfunction "IN-_6") (pintype "input"))
    )
    (net (code "64") (name "Net-(U206A-IN+)") (class "Default")
      (node (ref "C219") (pin "2") (pinfunction "2_2") (pintype "passive"))
      (node (ref "R217") (pin "1") (pinfunction "1_1") (pintype "passive"))
      (node (ref "U206") (pin "3") (pinfunction "IN+_3") (pintype "input"))
    )
    (net (code "65") (name "Net-(U206A-IN-)") (class "Default")
      (node (ref "R218") (pin "2") (pinfunction "2_2") (pintype "passive"))
      (node (ref "U206") (pin "1") (pinfunction "OUT_1") (pintype "output"))
      (node (ref "U206") (pin "2") (pinfunction "IN-_2") (pintype "input"))
    )
    (net (code "66") (name "Net-(U207B-OUT)") (class "Default")
      (node (ref "C216") (pin "2") (pinfunction "2_2") (pintype "passive"))
      (node (ref "R215") (pin "1") (pinfunction "1_1") (pintype "passive"))
      (node (ref "R219") (pin "1") (pinfunction "1_1") (pintype "passive"))
      (node (ref "U207") (pin "7") (pinfunction "OUT_7") (pintype "output"))
    )
    (net (code "67") (name "Net-(U208-C)") (class "Default")
      (node (ref "R222") (pin "2") (pinfunction "2_2") (pintype "passive"))
      (node (ref "U208") (pin "4") (pinfunction "C_4") (pintype "passive"))
    )
  )
)
